# RC_LOW_PASS_FILTER.net
KiCad netlist of a schematic drawn in EasyEDA
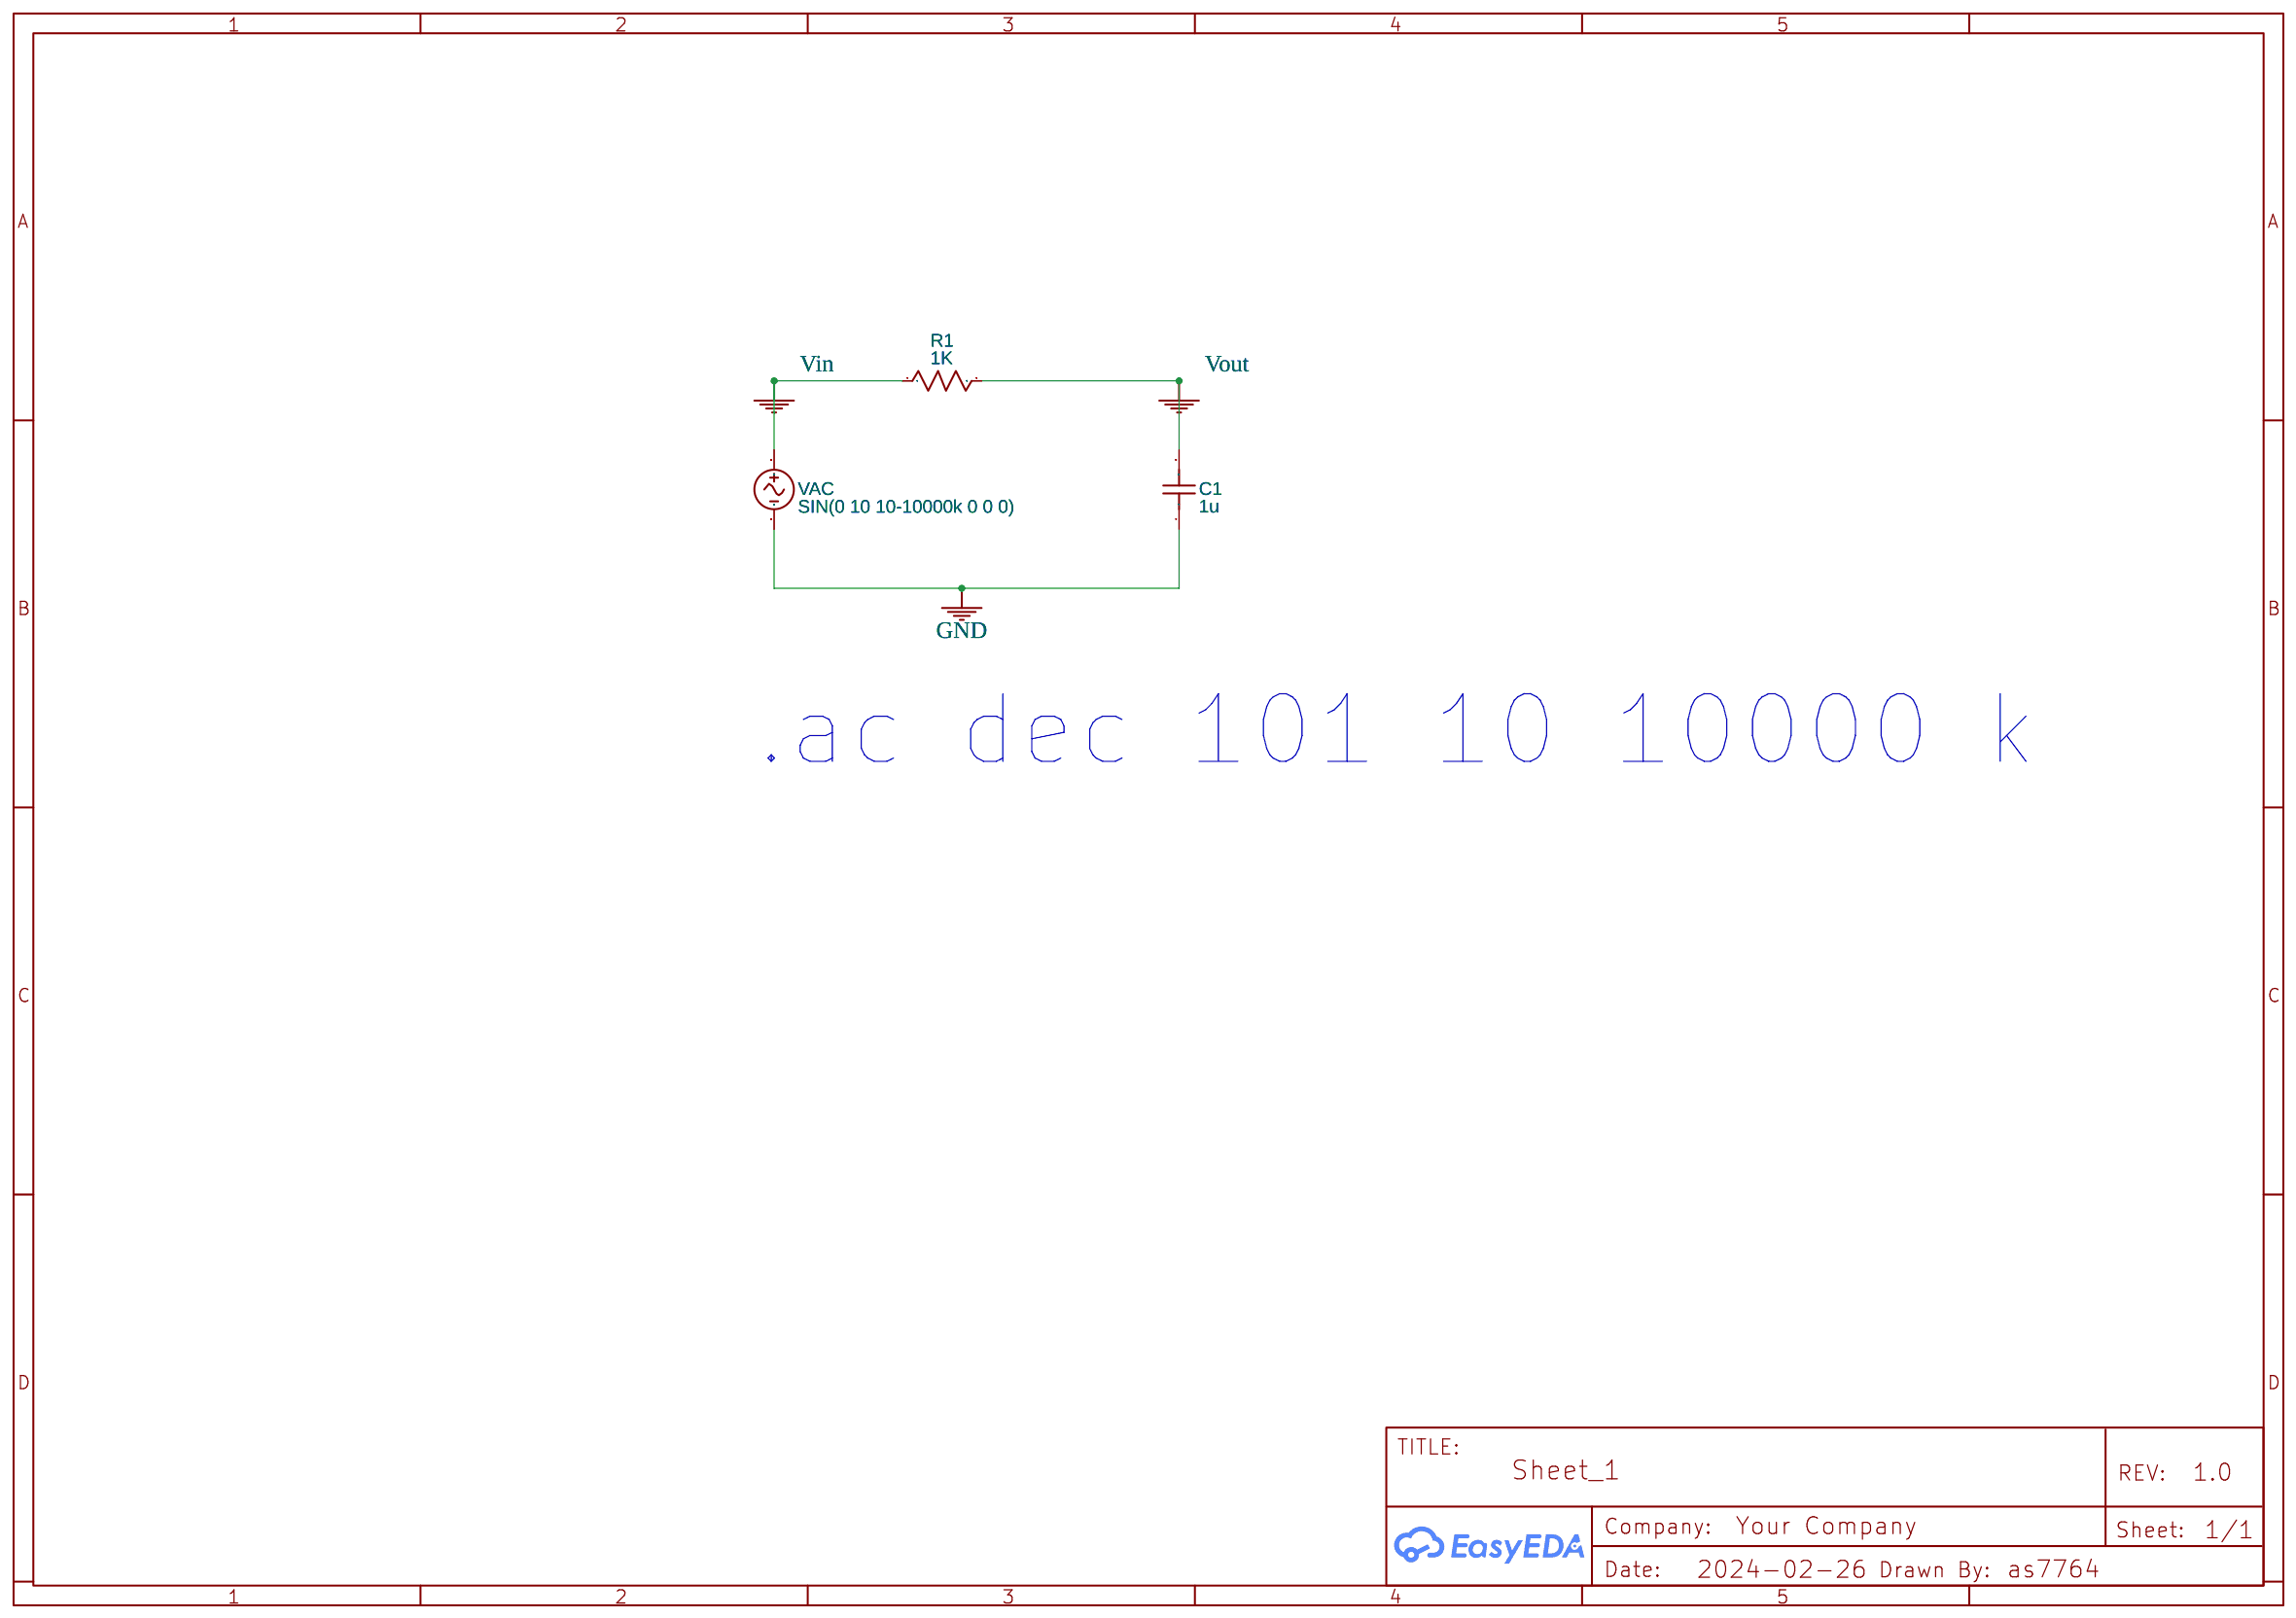
[diagram p0: schematic sheet]

(export (version "E")
  (design (tool "Eeschema 10.0.6"))
  (components
    (comp (ref "C1") (value "1u") (libsource (lib "") (part "Capacitor_US")))
    (comp (ref "R1") (value "1K") (libsource (lib "") (part "Resistor_US")))
    (comp (ref "VAC") (value "SIN(0 10 10-10000k 0 0 0)") (libsource (lib "") (part "VSin")))
  )
  (nets
    (net (code "1") (name "GND") (class "Default")
      (node (ref "C1") (pin "1") (pinfunction "1_1") (pintype "unspecified"))
      (node (ref "VAC") (pin "2") (pinfunction "2_2") (pintype "unspecified"))
    )
    (net (code "2") (name "Vin") (class "Default")
      (node (ref "R1") (pin "1") (pinfunction "1_1") (pintype "unspecified"))
      (node (ref "VAC") (pin "1") (pinfunction "1_1") (pintype "unspecified"))
    )
    (net (code "3") (name "Vout") (class "Default")
      (node (ref "C1") (pin "2") (pinfunction "2_2") (pintype "unspecified"))
      (node (ref "R1") (pin "2") (pinfunction "2_2") (pintype "unspecified"))
    )
  )
)
